# BD0006.net
KiCad netlist of a schematic drawn in EAGLE
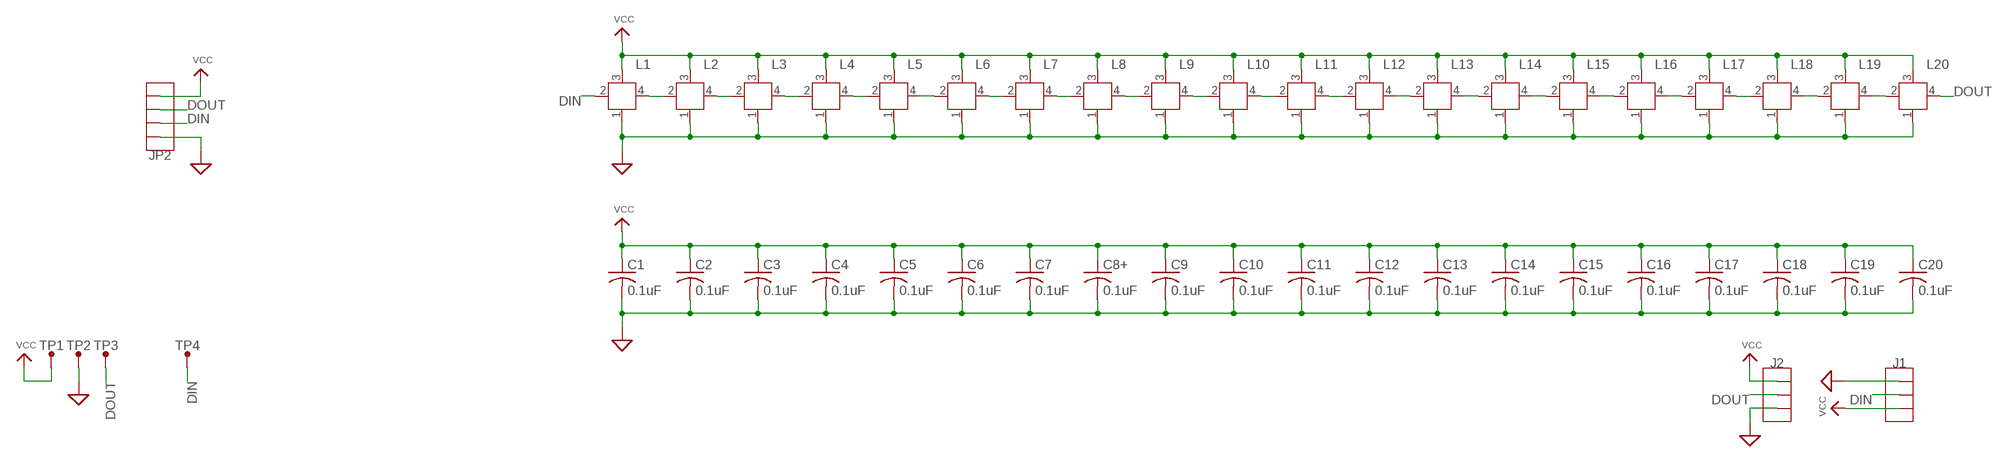
[diagram p0: schematic, sheet 1]

(export (version "E")
  (design (tool "Eeschema 10.0.6"))
  (components
    (comp (ref "C1")
      (value "0.1uF")
      (footprint "eagle-import:C0402")
      (libsource (lib "eagle-import") (part "C-USC0402"))
    )
    (comp (ref "C2")
      (value "0.1uF")
      (footprint "eagle-import:C0402")
      (libsource (lib "eagle-import") (part "C-USC0402"))
    )
    (comp (ref "C3")
      (value "0.1uF")
      (footprint "eagle-import:C0402")
      (libsource (lib "eagle-import") (part "C-USC0402"))
    )
    (comp (ref "C4")
      (value "0.1uF")
      (footprint "eagle-import:C0402")
      (libsource (lib "eagle-import") (part "C-USC0402"))
    )
    (comp (ref "C5")
      (value "0.1uF")
      (footprint "eagle-import:C0402")
      (libsource (lib "eagle-import") (part "C-USC0402"))
    )
    (comp (ref "C6")
      (value "0.1uF")
      (footprint "eagle-import:C0402")
      (libsource (lib "eagle-import") (part "C-USC0402"))
    )
    (comp (ref "C7")
      (value "0.1uF")
      (footprint "eagle-import:C0402")
      (libsource (lib "eagle-import") (part "C-USC0402"))
    )
    (comp (ref "C8+")
      (value "0.1uF")
      (footprint "eagle-import:C0402")
      (libsource (lib "eagle-import") (part "C-USC0402"))
    )
    (comp (ref "C9")
      (value "0.1uF")
      (footprint "eagle-import:C0402")
      (libsource (lib "eagle-import") (part "C-USC0402"))
    )
    (comp (ref "C10")
      (value "0.1uF")
      (footprint "eagle-import:C0402")
      (libsource (lib "eagle-import") (part "C-USC0402"))
    )
    (comp (ref "C11")
      (value "0.1uF")
      (footprint "eagle-import:C0402")
      (libsource (lib "eagle-import") (part "C-USC0402"))
    )
    (comp (ref "C12")
      (value "0.1uF")
      (footprint "eagle-import:C0402")
      (libsource (lib "eagle-import") (part "C-USC0402"))
    )
    (comp (ref "C13")
      (value "0.1uF")
      (footprint "eagle-import:C0402")
      (libsource (lib "eagle-import") (part "C-USC0402"))
    )
    (comp (ref "C14")
      (value "0.1uF")
      (footprint "eagle-import:C0402")
      (libsource (lib "eagle-import") (part "C-USC0402"))
    )
    (comp (ref "C15")
      (value "0.1uF")
      (footprint "eagle-import:C0402")
      (libsource (lib "eagle-import") (part "C-USC0402"))
    )
    (comp (ref "C16")
      (value "0.1uF")
      (footprint "eagle-import:C0402")
      (libsource (lib "eagle-import") (part "C-USC0402"))
    )
    (comp (ref "C17")
      (value "0.1uF")
      (footprint "eagle-import:C0402")
      (libsource (lib "eagle-import") (part "C-USC0402"))
    )
    (comp (ref "C18")
      (value "0.1uF")
      (footprint "eagle-import:C0402")
      (libsource (lib "eagle-import") (part "C-USC0402"))
    )
    (comp (ref "C19")
      (value "0.1uF")
      (footprint "eagle-import:C0402")
      (libsource (lib "eagle-import") (part "C-USC0402"))
    )
    (comp (ref "C20")
      (value "0.1uF")
      (footprint "eagle-import:C0402")
      (libsource (lib "eagle-import") (part "C-USC0402"))
    )
    (comp (ref "J1")
      (value "HEADER_1X3MALE")
      (footprint "eagle-import:M3SMD")
      (libsource (lib "eagle-import") (part "HEADER_1X3MALE"))
    )
    (comp (ref "J2")
      (value "HEADER_1X3FEMALE")
      (footprint "eagle-import:F3SMD")
      (libsource (lib "eagle-import") (part "HEADER_1X3FEMALE"))
    )
    (comp (ref "JP2")
      (value "HEADER_1X4S")
      (footprint "eagle-import:1X04")
      (libsource (lib "eagle-import") (part "HEADER_1X4S"))
    )
    (comp (ref "L1")
      (value "WS2812B")
      (footprint "eagle-import:SK6812")
      (libsource (lib "eagle-import") (part "WS2812B"))
    )
    (comp (ref "L2")
      (value "WS2812B")
      (footprint "eagle-import:SK6812")
      (libsource (lib "eagle-import") (part "WS2812B"))
    )
    (comp (ref "L3")
      (value "WS2812B")
      (footprint "eagle-import:SK6812")
      (libsource (lib "eagle-import") (part "WS2812B"))
    )
    (comp (ref "L4")
      (value "WS2812B")
      (footprint "eagle-import:SK6812")
      (libsource (lib "eagle-import") (part "WS2812B"))
    )
    (comp (ref "L5")
      (value "WS2812B")
      (footprint "eagle-import:SK6812")
      (libsource (lib "eagle-import") (part "WS2812B"))
    )
    (comp (ref "L6")
      (value "WS2812B")
      (footprint "eagle-import:SK6812")
      (libsource (lib "eagle-import") (part "WS2812B"))
    )
    (comp (ref "L7")
      (value "WS2812B")
      (footprint "eagle-import:SK6812")
      (libsource (lib "eagle-import") (part "WS2812B"))
    )
    (comp (ref "L8")
      (value "WS2812B")
      (footprint "eagle-import:SK6812")
      (libsource (lib "eagle-import") (part "WS2812B"))
    )
    (comp (ref "L9")
      (value "WS2812B")
      (footprint "eagle-import:SK6812")
      (libsource (lib "eagle-import") (part "WS2812B"))
    )
    (comp (ref "L10")
      (value "WS2812B")
      (footprint "eagle-import:SK6812")
      (libsource (lib "eagle-import") (part "WS2812B"))
    )
    (comp (ref "L11")
      (value "WS2812B")
      (footprint "eagle-import:SK6812")
      (libsource (lib "eagle-import") (part "WS2812B"))
    )
    (comp (ref "L12")
      (value "WS2812B")
      (footprint "eagle-import:SK6812")
      (libsource (lib "eagle-import") (part "WS2812B"))
    )
    (comp (ref "L13")
      (value "WS2812B")
      (footprint "eagle-import:SK6812")
      (libsource (lib "eagle-import") (part "WS2812B"))
    )
    (comp (ref "L14")
      (value "WS2812B")
      (footprint "eagle-import:SK6812")
      (libsource (lib "eagle-import") (part "WS2812B"))
    )
    (comp (ref "L15")
      (value "WS2812B")
      (footprint "eagle-import:SK6812")
      (libsource (lib "eagle-import") (part "WS2812B"))
    )
    (comp (ref "L16")
      (value "WS2812B")
      (footprint "eagle-import:SK6812")
      (libsource (lib "eagle-import") (part "WS2812B"))
    )
    (comp (ref "L17")
      (value "WS2812B")
      (footprint "eagle-import:SK6812")
      (libsource (lib "eagle-import") (part "WS2812B"))
    )
    (comp (ref "L18")
      (value "WS2812B")
      (footprint "eagle-import:SK6812")
      (libsource (lib "eagle-import") (part "WS2812B"))
    )
    (comp (ref "L19")
      (value "WS2812B")
      (footprint "eagle-import:SK6812")
      (libsource (lib "eagle-import") (part "WS2812B"))
    )
    (comp (ref "L20")
      (value "WS2812B")
      (footprint "eagle-import:SK6812")
      (libsource (lib "eagle-import") (part "WS2812B"))
    )
    (comp (ref "TP1")
      (value "VCC")
      (footprint "eagle-import:TEST_POINT")
      (libsource (lib "eagle-import") (part "TEST_POINT"))
    )
    (comp (ref "TP2")
      (value "GND")
      (footprint "eagle-import:TEST_POINT")
      (libsource (lib "eagle-import") (part "TEST_POINT"))
    )
    (comp (ref "TP3")
      (value "DOUT")
      (footprint "eagle-import:TEST_POINT")
      (libsource (lib "eagle-import") (part "TEST_POINT"))
    )
    (comp (ref "TP4")
      (value "DIN")
      (footprint "eagle-import:TEST_POINT")
      (libsource (lib "eagle-import") (part "TEST_POINT"))
    )
  )
  (nets
    (net (code "1") (name "/DIN") (class "Default")
      (node (ref "J1") (pin "2") (pinfunction "P$2_2") (pintype "bidirectional"))
      (node (ref "JP2") (pin "2") (pinfunction "P$2_2") (pintype "bidirectional"))
      (node (ref "L1") (pin "2") (pinfunction "DIN_2") (pintype "bidirectional"))
      (node (ref "TP4") (pin "P$1") (pinfunction "P$1_P$1") (pintype "input"))
    )
    (net (code "2") (name "/DOUT") (class "Default")
      (node (ref "J2") (pin "2A") (pinfunction "P$2_2A") (pintype "bidirectional"))
      (node (ref "J2") (pin "2B") (pinfunction "P$2_2B") (pintype "bidirectional"))
      (node (ref "JP2") (pin "3") (pinfunction "P$3_3") (pintype "bidirectional"))
      (node (ref "L20") (pin "4") (pinfunction "DOUT_4") (pintype "bidirectional"))
      (node (ref "TP3") (pin "P$1") (pinfunction "P$1_P$1") (pintype "input"))
    )
    (net (code "3") (name "Net-(L1-DOUT)") (class "Default")
      (node (ref "L1") (pin "4") (pinfunction "DOUT_4") (pintype "bidirectional"))
      (node (ref "L2") (pin "2") (pinfunction "DIN_2") (pintype "bidirectional"))
    )
    (net (code "4") (name "Net-(L2-DOUT)") (class "Default")
      (node (ref "L2") (pin "4") (pinfunction "DOUT_4") (pintype "bidirectional"))
      (node (ref "L3") (pin "2") (pinfunction "DIN_2") (pintype "bidirectional"))
    )
    (net (code "5") (name "Net-(L3-DOUT)") (class "Default")
      (node (ref "L3") (pin "4") (pinfunction "DOUT_4") (pintype "bidirectional"))
      (node (ref "L4") (pin "2") (pinfunction "DIN_2") (pintype "bidirectional"))
    )
    (net (code "6") (name "Net-(L4-DOUT)") (class "Default")
      (node (ref "L4") (pin "4") (pinfunction "DOUT_4") (pintype "bidirectional"))
      (node (ref "L5") (pin "2") (pinfunction "DIN_2") (pintype "bidirectional"))
    )
    (net (code "7") (name "Net-(L5-DOUT)") (class "Default")
      (node (ref "L5") (pin "4") (pinfunction "DOUT_4") (pintype "bidirectional"))
      (node (ref "L6") (pin "2") (pinfunction "DIN_2") (pintype "bidirectional"))
    )
    (net (code "8") (name "Net-(L6-DOUT)") (class "Default")
      (node (ref "L6") (pin "4") (pinfunction "DOUT_4") (pintype "bidirectional"))
      (node (ref "L7") (pin "2") (pinfunction "DIN_2") (pintype "bidirectional"))
    )
    (net (code "9") (name "Net-(L7-DOUT)") (class "Default")
      (node (ref "L7") (pin "4") (pinfunction "DOUT_4") (pintype "bidirectional"))
      (node (ref "L8") (pin "2") (pinfunction "DIN_2") (pintype "bidirectional"))
    )
    (net (code "10") (name "Net-(L8-DOUT)") (class "Default")
      (node (ref "L8") (pin "4") (pinfunction "DOUT_4") (pintype "bidirectional"))
      (node (ref "L9") (pin "2") (pinfunction "DIN_2") (pintype "bidirectional"))
    )
    (net (code "11") (name "Net-(L10-DIN)") (class "Default")
      (node (ref "L10") (pin "2") (pinfunction "DIN_2") (pintype "bidirectional"))
      (node (ref "L9") (pin "4") (pinfunction "DOUT_4") (pintype "bidirectional"))
    )
    (net (code "12") (name "Net-(L10-DOUT)") (class "Default")
      (node (ref "L10") (pin "4") (pinfunction "DOUT_4") (pintype "bidirectional"))
      (node (ref "L11") (pin "2") (pinfunction "DIN_2") (pintype "bidirectional"))
    )
    (net (code "13") (name "Net-(L11-DOUT)") (class "Default")
      (node (ref "L11") (pin "4") (pinfunction "DOUT_4") (pintype "bidirectional"))
      (node (ref "L12") (pin "2") (pinfunction "DIN_2") (pintype "bidirectional"))
    )
    (net (code "14") (name "Net-(L12-DOUT)") (class "Default")
      (node (ref "L12") (pin "4") (pinfunction "DOUT_4") (pintype "bidirectional"))
      (node (ref "L13") (pin "2") (pinfunction "DIN_2") (pintype "bidirectional"))
    )
    (net (code "15") (name "Net-(L13-DOUT)") (class "Default")
      (node (ref "L13") (pin "4") (pinfunction "DOUT_4") (pintype "bidirectional"))
      (node (ref "L14") (pin "2") (pinfunction "DIN_2") (pintype "bidirectional"))
    )
    (net (code "16") (name "Net-(L14-DOUT)") (class "Default")
      (node (ref "L14") (pin "4") (pinfunction "DOUT_4") (pintype "bidirectional"))
      (node (ref "L15") (pin "2") (pinfunction "DIN_2") (pintype "bidirectional"))
    )
    (net (code "17") (name "Net-(L15-DOUT)") (class "Default")
      (node (ref "L15") (pin "4") (pinfunction "DOUT_4") (pintype "bidirectional"))
      (node (ref "L16") (pin "2") (pinfunction "DIN_2") (pintype "bidirectional"))
    )
    (net (code "18") (name "Net-(L16-DOUT)") (class "Default")
      (node (ref "L16") (pin "4") (pinfunction "DOUT_4") (pintype "bidirectional"))
      (node (ref "L17") (pin "2") (pinfunction "DIN_2") (pintype "bidirectional"))
    )
    (net (code "19") (name "Net-(L17-DOUT)") (class "Default")
      (node (ref "L17") (pin "4") (pinfunction "DOUT_4") (pintype "bidirectional"))
      (node (ref "L18") (pin "2") (pinfunction "DIN_2") (pintype "bidirectional"))
    )
    (net (code "20") (name "Net-(L18-DOUT)") (class "Default")
      (node (ref "L18") (pin "4") (pinfunction "DOUT_4") (pintype "bidirectional"))
      (node (ref "L19") (pin "2") (pinfunction "DIN_2") (pintype "bidirectional"))
    )
    (net (code "21") (name "Net-(L19-DOUT)") (class "Default")
      (node (ref "L19") (pin "4") (pinfunction "DOUT_4") (pintype "bidirectional"))
      (node (ref "L20") (pin "2") (pinfunction "DIN_2") (pintype "bidirectional"))
    )
    (net (code "22") (name "SUP") (class "Default")
      (node (ref "C1") (pin "2") (pinfunction "2_2") (pintype "passive"))
      (node (ref "C10") (pin "2") (pinfunction "2_2") (pintype "passive"))
      (node (ref "C11") (pin "2") (pinfunction "2_2") (pintype "passive"))
      (node (ref "C12") (pin "2") (pinfunction "2_2") (pintype "passive"))
      (node (ref "C13") (pin "2") (pinfunction "2_2") (pintype "passive"))
      (node (ref "C14") (pin "2") (pinfunction "2_2") (pintype "passive"))
      (node (ref "C15") (pin "2") (pinfunction "2_2") (pintype "passive"))
      (node (ref "C16") (pin "2") (pinfunction "2_2") (pintype "passive"))
      (node (ref "C17") (pin "2") (pinfunction "2_2") (pintype "passive"))
      (node (ref "C18") (pin "2") (pinfunction "2_2") (pintype "passive"))
      (node (ref "C19") (pin "2") (pinfunction "2_2") (pintype "passive"))
      (node (ref "C2") (pin "2") (pinfunction "2_2") (pintype "passive"))
      (node (ref "C20") (pin "2") (pinfunction "2_2") (pintype "passive"))
      (node (ref "C3") (pin "2") (pinfunction "2_2") (pintype "passive"))
      (node (ref "C4") (pin "2") (pinfunction "2_2") (pintype "passive"))
      (node (ref "C5") (pin "2") (pinfunction "2_2") (pintype "passive"))
      (node (ref "C6") (pin "2") (pinfunction "2_2") (pintype "passive"))
      (node (ref "C7") (pin "2") (pinfunction "2_2") (pintype "passive"))
      (node (ref "C8+") (pin "2") (pinfunction "2_2") (pintype "passive"))
      (node (ref "C9") (pin "2") (pinfunction "2_2") (pintype "passive"))
      (node (ref "J1") (pin "1") (pinfunction "P$1_1") (pintype "bidirectional"))
      (node (ref "J2") (pin "3A") (pinfunction "P$3_3A") (pintype "bidirectional"))
      (node (ref "J2") (pin "3B") (pinfunction "P$3_3B") (pintype "bidirectional"))
      (node (ref "JP2") (pin "1") (pinfunction "P$1_1") (pintype "bidirectional"))
      (node (ref "L1") (pin "1") (pinfunction "VSS_1") (pintype "bidirectional"))
      (node (ref "L10") (pin "1") (pinfunction "VSS_1") (pintype "bidirectional"))
      (node (ref "L11") (pin "1") (pinfunction "VSS_1") (pintype "bidirectional"))
      (node (ref "L12") (pin "1") (pinfunction "VSS_1") (pintype "bidirectional"))
      (node (ref "L13") (pin "1") (pinfunction "VSS_1") (pintype "bidirectional"))
      (node (ref "L14") (pin "1") (pinfunction "VSS_1") (pintype "bidirectional"))
      (node (ref "L15") (pin "1") (pinfunction "VSS_1") (pintype "bidirectional"))
      (node (ref "L16") (pin "1") (pinfunction "VSS_1") (pintype "bidirectional"))
      (node (ref "L17") (pin "1") (pinfunction "VSS_1") (pintype "bidirectional"))
      (node (ref "L18") (pin "1") (pinfunction "VSS_1") (pintype "bidirectional"))
      (node (ref "L19") (pin "1") (pinfunction "VSS_1") (pintype "bidirectional"))
      (node (ref "L2") (pin "1") (pinfunction "VSS_1") (pintype "bidirectional"))
      (node (ref "L20") (pin "1") (pinfunction "VSS_1") (pintype "bidirectional"))
      (node (ref "L3") (pin "1") (pinfunction "VSS_1") (pintype "bidirectional"))
      (node (ref "L4") (pin "1") (pinfunction "VSS_1") (pintype "bidirectional"))
      (node (ref "L5") (pin "1") (pinfunction "VSS_1") (pintype "bidirectional"))
      (node (ref "L6") (pin "1") (pinfunction "VSS_1") (pintype "bidirectional"))
      (node (ref "L7") (pin "1") (pinfunction "VSS_1") (pintype "bidirectional"))
      (node (ref "L8") (pin "1") (pinfunction "VSS_1") (pintype "bidirectional"))
      (node (ref "L9") (pin "1") (pinfunction "VSS_1") (pintype "bidirectional"))
      (node (ref "TP2") (pin "P$1") (pinfunction "P$1_P$1") (pintype "input"))
    )
    (net (code "23") (name "VCC") (class "Default")
      (node (ref "C1") (pin "1") (pinfunction "1_1") (pintype "passive"))
      (node (ref "C10") (pin "1") (pinfunction "1_1") (pintype "passive"))
      (node (ref "C11") (pin "1") (pinfunction "1_1") (pintype "passive"))
      (node (ref "C12") (pin "1") (pinfunction "1_1") (pintype "passive"))
      (node (ref "C13") (pin "1") (pinfunction "1_1") (pintype "passive"))
      (node (ref "C14") (pin "1") (pinfunction "1_1") (pintype "passive"))
      (node (ref "C15") (pin "1") (pinfunction "1_1") (pintype "passive"))
      (node (ref "C16") (pin "1") (pinfunction "1_1") (pintype "passive"))
      (node (ref "C17") (pin "1") (pinfunction "1_1") (pintype "passive"))
      (node (ref "C18") (pin "1") (pinfunction "1_1") (pintype "passive"))
      (node (ref "C19") (pin "1") (pinfunction "1_1") (pintype "passive"))
      (node (ref "C2") (pin "1") (pinfunction "1_1") (pintype "passive"))
      (node (ref "C20") (pin "1") (pinfunction "1_1") (pintype "passive"))
      (node (ref "C3") (pin "1") (pinfunction "1_1") (pintype "passive"))
      (node (ref "C4") (pin "1") (pinfunction "1_1") (pintype "passive"))
      (node (ref "C5") (pin "1") (pinfunction "1_1") (pintype "passive"))
      (node (ref "C6") (pin "1") (pinfunction "1_1") (pintype "passive"))
      (node (ref "C7") (pin "1") (pinfunction "1_1") (pintype "passive"))
      (node (ref "C8+") (pin "1") (pinfunction "1_1") (pintype "passive"))
      (node (ref "C9") (pin "1") (pinfunction "1_1") (pintype "passive"))
      (node (ref "J1") (pin "3") (pinfunction "P$3_3") (pintype "bidirectional"))
      (node (ref "J2") (pin "1A") (pinfunction "P$1_1A") (pintype "bidirectional"))
      (node (ref "J2") (pin "1B") (pinfunction "P$1_1B") (pintype "bidirectional"))
      (node (ref "JP2") (pin "4") (pinfunction "P$4_4") (pintype "bidirectional"))
      (node (ref "L1") (pin "3") (pinfunction "VDD_3") (pintype "bidirectional"))
      (node (ref "L10") (pin "3") (pinfunction "VDD_3") (pintype "bidirectional"))
      (node (ref "L11") (pin "3") (pinfunction "VDD_3") (pintype "bidirectional"))
      (node (ref "L12") (pin "3") (pinfunction "VDD_3") (pintype "bidirectional"))
      (node (ref "L13") (pin "3") (pinfunction "VDD_3") (pintype "bidirectional"))
      (node (ref "L14") (pin "3") (pinfunction "VDD_3") (pintype "bidirectional"))
      (node (ref "L15") (pin "3") (pinfunction "VDD_3") (pintype "bidirectional"))
      (node (ref "L16") (pin "3") (pinfunction "VDD_3") (pintype "bidirectional"))
      (node (ref "L17") (pin "3") (pinfunction "VDD_3") (pintype "bidirectional"))
      (node (ref "L18") (pin "3") (pinfunction "VDD_3") (pintype "bidirectional"))
      (node (ref "L19") (pin "3") (pinfunction "VDD_3") (pintype "bidirectional"))
      (node (ref "L2") (pin "3") (pinfunction "VDD_3") (pintype "bidirectional"))
      (node (ref "L20") (pin "3") (pinfunction "VDD_3") (pintype "bidirectional"))
      (node (ref "L3") (pin "3") (pinfunction "VDD_3") (pintype "bidirectional"))
      (node (ref "L4") (pin "3") (pinfunction "VDD_3") (pintype "bidirectional"))
      (node (ref "L5") (pin "3") (pinfunction "VDD_3") (pintype "bidirectional"))
      (node (ref "L6") (pin "3") (pinfunction "VDD_3") (pintype "bidirectional"))
      (node (ref "L7") (pin "3") (pinfunction "VDD_3") (pintype "bidirectional"))
      (node (ref "L8") (pin "3") (pinfunction "VDD_3") (pintype "bidirectional"))
      (node (ref "L9") (pin "3") (pinfunction "VDD_3") (pintype "bidirectional"))
      (node (ref "TP1") (pin "P$1") (pinfunction "P$1_P$1") (pintype "input"))
    )
  )
)
